# Arduino_Nano_Pinouts.net
KiCad netlist of a schematic drawn in Altium Designer
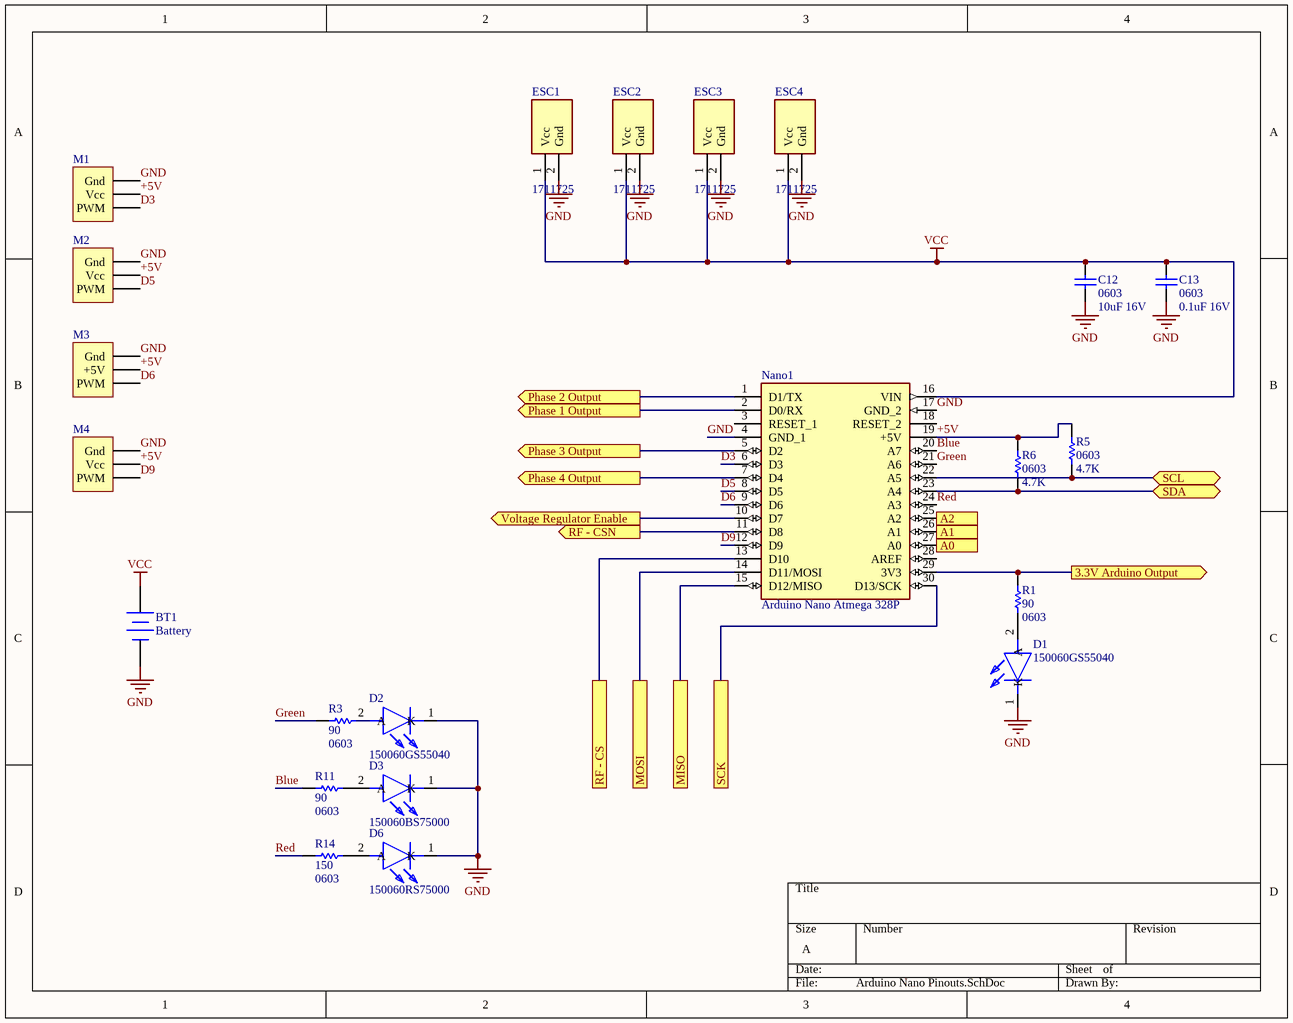
[diagram p0: Arduino Nano Pinouts.SchDoc]

(export (version "E")
  (design (tool "Eeschema 10.0.6"))
  (components
    (comp (ref "BT1")
      (value "Battery")
      (footprint "12AWGBATTCONNECTOR")
      (description "Multicell Battery")
      (fields (field (name "PUBLISHER") "Altium Limited"))
      (libsource (lib "Miscellaneous Devices") (part "Battery"))
    )
    (comp (ref "C12")
      (value "0603")
      (footprint "SMD-0603C")
      (description "Capacitor")
      (fields (field (name "ALTIUM_VALUE") "10uF 16V") (field (name "PUBLISHER") "Altium Limited"))
      (libsource (lib "Miscellaneous Devices") (part "Cap"))
    )
    (comp (ref "C13")
      (value "0603")
      (footprint "SMD-0603C")
      (description "Capacitor")
      (fields (field (name "ALTIUM_VALUE") "0.1uF 16V") (field (name "PUBLISHER") "Altium Limited"))
      (libsource (lib "Miscellaneous Devices") (part "Cap"))
    )
    (comp (ref "D1")
      (value "150060GS55040")
      (footprint "SamacSys:LEDC1608X50N")
      (description "LED")
      (fields
        (field (name "MOUSER PART NUMBER") "710-150060GS55040")
        (field (name "RS PART NUMBER") "1766068P")
      )
      (libsource (lib "*") (part "150060GS55040"))
    )
    (comp (ref "D2")
      (value "150060GS55040")
      (footprint "SamacSys:LEDC1608X50N")
      (description "LED")
      (fields
        (field (name "MOUSER PART NUMBER") "710-150060GS55040")
        (field (name "RS PART NUMBER") "1766068P")
      )
      (libsource (lib "*") (part "150060GS55040"))
    )
    (comp (ref "D3")
      (value "150060BS75000")
      (footprint "SamacSys:LEDC1608X80N")
      (description "LED")
      (fields
        (field (name "MOUSER PART NUMBER") "710-150060BS75000")
        (field (name "RS PART NUMBER") "8154206P")
      )
      (libsource (lib "*") (part "150060BS75000"))
    )
    (comp (ref "D6")
      (value "150060RS75000")
      (footprint "SamacSys:LEDC1608X80N")
      (description "LED")
      (fields
        (field (name "MOUSER PART NUMBER") "710-150060RS75000")
        (field (name "RS PART NUMBER") "8154203P")
      )
      (libsource (lib "*") (part "150060RS75000"))
    )
    (comp (ref "ESC1")
      (value "1711725")
      (footprint "SamacSys:PHEONIX-5.08PITCH-2PIN")
      (description "Integrated Circuit")
      (fields (field (name "MOUSER PART NUMBER") "651-1711725") (field (name "RS PART NUMBER") "1895843"))
      (libsource (lib "*") (part "1711725"))
    )
    (comp (ref "ESC2")
      (value "1711725")
      (footprint "SamacSys:PHEONIX-5.08PITCH-2PIN")
      (description "Integrated Circuit")
      (fields (field (name "MOUSER PART NUMBER") "651-1711725") (field (name "RS PART NUMBER") "1895843"))
      (libsource (lib "*") (part "1711725"))
    )
    (comp (ref "ESC3")
      (value "1711725")
      (footprint "SamacSys:PHEONIX-5.08PITCH-2PIN")
      (description "Integrated Circuit")
      (fields (field (name "MOUSER PART NUMBER") "651-1711725") (field (name "RS PART NUMBER") "1895843"))
      (libsource (lib "*") (part "1711725"))
    )
    (comp (ref "ESC4")
      (value "1711725")
      (footprint "SamacSys:PHEONIX-5.08PITCH-2PIN")
      (description "Integrated Circuit")
      (fields (field (name "MOUSER PART NUMBER") "651-1711725") (field (name "RS PART NUMBER") "1895843"))
      (libsource (lib "*") (part "1711725"))
    )
    (comp (ref "M1")
      (value "~")
      (footprint "*TE_3-644695-3")
      (description "Header, 3-Pin")
      (fields (field (name "PUBLISHER") "Altium Limited"))
      (libsource (lib "Miscellaneous Connectors") (part "Header 3"))
    )
    (comp (ref "M2")
      (value "~")
      (footprint "*TE_3-644695-3")
      (description "Header, 3-Pin")
      (fields (field (name "PUBLISHER") "Altium Limited"))
      (libsource (lib "Miscellaneous Connectors") (part "Header 3"))
    )
    (comp (ref "M3")
      (value "~")
      (footprint "*TE_3-644695-3")
      (description "Header, 3-Pin")
      (fields (field (name "PUBLISHER") "Altium Limited"))
      (libsource (lib "Miscellaneous Connectors") (part "Header 3"))
    )
    (comp (ref "M4")
      (value "~")
      (footprint "*TE_3-644695-3")
      (description "Header, 3-Pin")
      (fields (field (name "PUBLISHER") "Altium Limited"))
      (libsource (lib "Miscellaneous Connectors") (part "Header 3"))
    )
    (comp (ref "Nano1")
      (value "Arduino Nano Atmega 328P")
      (footprint "ARDNanoINV")
      (description "Integrated Circuit")
      (fields
        (field (name "MANUFACTURER_PART_NUMBER") "ARDNanoINV")
        (field (name "MOUSER PART NUMBER") "992-ARD-NANO30")
      )
      (libsource (lib "*") (part "ARDNanoINV"))
    )
    (comp (ref "R1")
      (value "90")
      (footprint "SMD-0603-RES")
      (description "Resistor")
      (fields (field (name "ALTIUM_VALUE") "0603") (field (name "PUBLISHER") "Altium Limited"))
      (libsource (lib "Miscellaneous Devices") (part "Res1"))
    )
    (comp (ref "R3")
      (value "90")
      (footprint "SMD-0603-RES")
      (description "Resistor")
      (fields (field (name "ALTIUM_VALUE") "0603") (field (name "PUBLISHER") "Altium Limited"))
      (libsource (lib "Miscellaneous Devices") (part "Res1"))
    )
    (comp (ref "R5")
      (value "0603")
      (footprint "SMD-0603C")
      (description "Resistor")
      (fields (field (name "ALTIUM_VALUE") "4.7K") (field (name "PUBLISHER") "Altium Limited"))
      (libsource (lib "Miscellaneous Devices") (part "Res1"))
    )
    (comp (ref "R6")
      (value "0603")
      (footprint "SMD-0603-RES")
      (description "Resistor")
      (fields (field (name "ALTIUM_VALUE") "4.7K") (field (name "PUBLISHER") "Altium Limited"))
      (libsource (lib "Miscellaneous Devices") (part "Res1"))
    )
    (comp (ref "R11")
      (value "90")
      (footprint "SMD-0603-RES")
      (description "Resistor")
      (fields (field (name "ALTIUM_VALUE") "0603") (field (name "PUBLISHER") "Altium Limited"))
      (libsource (lib "Miscellaneous Devices") (part "Res1"))
    )
    (comp (ref "R14")
      (value "150")
      (footprint "SMD-0603-RES")
      (description "Resistor")
      (fields (field (name "ALTIUM_VALUE") "0603") (field (name "PUBLISHER") "Altium Limited"))
      (libsource (lib "Miscellaneous Devices") (part "Res1"))
    )
  )
  (nets
    (net (code "1") (name "/+5V") (class "Default")
      (node (ref "M1") (pin "2") (pinfunction "Vcc_2") (pintype "passive"))
      (node (ref "M2") (pin "2") (pinfunction "Vcc_2") (pintype "passive"))
      (node (ref "M3") (pin "2") (pinfunction "Vcc_2") (pintype "passive"))
      (node (ref "M4") (pin "2") (pinfunction "Vcc_2") (pintype "passive"))
      (node (ref "Nano1") (pin "19") (pinfunction "+5V_19") (pintype "power_in"))
      (node (ref "R5") (pin "2") (pinfunction "2_2") (pintype "passive"))
      (node (ref "R6") (pin "2") (pinfunction "2_2") (pintype "passive"))
    )
    (net (code "2") (name "/3.3V Arduino Output") (class "Default")
      (node (ref "Nano1") (pin "29") (pinfunction "3V3_29") (pintype "bidirectional"))
      (node (ref "R1") (pin "1") (pinfunction "1_1") (pintype "passive"))
    )
    (net (code "3") (name "/A0") (class "Default")
      (node (ref "Nano1") (pin "27") (pinfunction "A0_27") (pintype "bidirectional"))
    )
    (net (code "4") (name "/A1") (class "Default")
      (node (ref "Nano1") (pin "26") (pinfunction "A1_26") (pintype "bidirectional"))
    )
    (net (code "5") (name "/A2") (class "Default")
      (node (ref "Nano1") (pin "25") (pinfunction "A2_25") (pintype "bidirectional"))
    )
    (net (code "6") (name "/Blue") (class "Default")
      (node (ref "Nano1") (pin "20") (pinfunction "A7_20") (pintype "bidirectional"))
      (node (ref "R11") (pin "1") (pinfunction "1_1") (pintype "passive"))
    )
    (net (code "7") (name "/D3") (class "Default")
      (node (ref "M1") (pin "1") (pinfunction "PWM_1") (pintype "passive"))
      (node (ref "Nano1") (pin "6") (pinfunction "D3_6") (pintype "bidirectional"))
    )
    (net (code "8") (name "/D5") (class "Default")
      (node (ref "M2") (pin "1") (pinfunction "PWM_1") (pintype "passive"))
      (node (ref "Nano1") (pin "8") (pinfunction "D5_8") (pintype "bidirectional"))
    )
    (net (code "9") (name "/D6") (class "Default")
      (node (ref "M3") (pin "1") (pinfunction "PWM_1") (pintype "passive"))
      (node (ref "Nano1") (pin "9") (pinfunction "D6_9") (pintype "bidirectional"))
    )
    (net (code "10") (name "/D9") (class "Default")
      (node (ref "M4") (pin "1") (pinfunction "PWM_1") (pintype "passive"))
      (node (ref "Nano1") (pin "12") (pinfunction "D9_12") (pintype "bidirectional"))
    )
    (net (code "11") (name "/Green") (class "Default")
      (node (ref "Nano1") (pin "21") (pinfunction "A6_21") (pintype "bidirectional"))
      (node (ref "R3") (pin "1") (pinfunction "1_1") (pintype "passive"))
    )
    (net (code "12") (name "/MISO") (class "Default")
      (node (ref "Nano1") (pin "15") (pinfunction "D12/MISO_15") (pintype "bidirectional"))
    )
    (net (code "13") (name "/MOSI") (class "Default")
      (node (ref "Nano1") (pin "14") (pinfunction "D11/MOSI_14") (pintype "power_in"))
    )
    (net (code "14") (name "/Phase 1 Output") (class "Default")
      (node (ref "Nano1") (pin "2") (pinfunction "D0/RX_2") (pintype "power_in"))
    )
    (net (code "15") (name "/Phase 2 Output") (class "Default")
      (node (ref "Nano1") (pin "1") (pinfunction "D1/TX_1") (pintype "power_in"))
    )
    (net (code "16") (name "/Phase 3 Output") (class "Default")
      (node (ref "Nano1") (pin "5") (pinfunction "D2_5") (pintype "bidirectional"))
    )
    (net (code "17") (name "/Phase 4 Output") (class "Default")
      (node (ref "Nano1") (pin "7") (pinfunction "D4_7") (pintype "bidirectional"))
    )
    (net (code "18") (name "/RF - CS") (class "Default")
      (node (ref "Nano1") (pin "13") (pinfunction "D10_13") (pintype "passive"))
    )
    (net (code "19") (name "/RF - CSN") (class "Default")
      (node (ref "Nano1") (pin "11") (pinfunction "D8_11") (pintype "bidirectional"))
    )
    (net (code "20") (name "/Red") (class "Default")
      (node (ref "Nano1") (pin "24") (pinfunction "A3_24") (pintype "bidirectional"))
      (node (ref "R14") (pin "1") (pinfunction "1_1") (pintype "passive"))
    )
    (net (code "21") (name "/SCK") (class "Default")
      (node (ref "Nano1") (pin "30") (pinfunction "D13/SCK_30") (pintype "bidirectional"))
    )
    (net (code "22") (name "/SCL") (class "Default")
      (node (ref "Nano1") (pin "22") (pinfunction "A5_22") (pintype "bidirectional"))
      (node (ref "R5") (pin "1") (pinfunction "1_1") (pintype "passive"))
    )
    (net (code "23") (name "/SDA") (class "Default")
      (node (ref "Nano1") (pin "23") (pinfunction "A4_23") (pintype "bidirectional"))
      (node (ref "R6") (pin "1") (pinfunction "1_1") (pintype "passive"))
    )
    (net (code "24") (name "/Voltage Regulator Enable") (class "Default")
      (node (ref "Nano1") (pin "10") (pinfunction "D7_10") (pintype "bidirectional"))
    )
    (net (code "25") (name "GND") (class "Default")
      (node (ref "BT1") (pin "2") (pinfunction "-_2") (pintype "passive"))
      (node (ref "C12") (pin "1") (pinfunction "1_1") (pintype "passive"))
      (node (ref "C13") (pin "1") (pinfunction "1_1") (pintype "passive"))
      (node (ref "D1") (pin "1") (pinfunction "K_1") (pintype "passive"))
      (node (ref "D2") (pin "1") (pinfunction "K_1") (pintype "passive"))
      (node (ref "D3") (pin "1") (pinfunction "K_1") (pintype "passive"))
      (node (ref "D6") (pin "1") (pinfunction "K_1") (pintype "passive"))
      (node (ref "ESC1") (pin "2") (pinfunction "Gnd_2") (pintype "passive"))
      (node (ref "ESC2") (pin "2") (pinfunction "Gnd_2") (pintype "passive"))
      (node (ref "ESC3") (pin "2") (pinfunction "Gnd_2") (pintype "passive"))
      (node (ref "ESC4") (pin "2") (pinfunction "Gnd_2") (pintype "passive"))
      (node (ref "M1") (pin "3") (pinfunction "Gnd_3") (pintype "passive"))
      (node (ref "M2") (pin "3") (pinfunction "Gnd_3") (pintype "passive"))
      (node (ref "M3") (pin "3") (pinfunction "Gnd_3") (pintype "passive"))
      (node (ref "M4") (pin "3") (pinfunction "Gnd_3") (pintype "passive"))
      (node (ref "Nano1") (pin "17") (pinfunction "GND_2_17") (pintype "input"))
      (node (ref "Nano1") (pin "4") (pinfunction "GND_1_4") (pintype "power_in"))
    )
    (net (code "26") (name "Net-(D1-A)") (class "Default")
      (node (ref "D1") (pin "2") (pinfunction "A_2") (pintype "passive"))
      (node (ref "R1") (pin "2") (pinfunction "2_2") (pintype "passive"))
    )
    (net (code "27") (name "Net-(D2-A)") (class "Default")
      (node (ref "D2") (pin "2") (pinfunction "A_2") (pintype "passive"))
      (node (ref "R3") (pin "2") (pinfunction "2_2") (pintype "passive"))
    )
    (net (code "28") (name "Net-(D3-A)") (class "Default")
      (node (ref "D3") (pin "2") (pinfunction "A_2") (pintype "passive"))
      (node (ref "R11") (pin "2") (pinfunction "2_2") (pintype "passive"))
    )
    (net (code "29") (name "Net-(D6-A)") (class "Default")
      (node (ref "D6") (pin "2") (pinfunction "A_2") (pintype "passive"))
      (node (ref "R14") (pin "2") (pinfunction "2_2") (pintype "passive"))
    )
    (net (code "30") (name "VCC") (class "Default")
      (node (ref "BT1") (pin "1") (pinfunction "+_1") (pintype "passive"))
      (node (ref "C12") (pin "2") (pinfunction "2_2") (pintype "passive"))
      (node (ref "C13") (pin "2") (pinfunction "2_2") (pintype "passive"))
      (node (ref "ESC1") (pin "1") (pinfunction "Vcc_1") (pintype "passive"))
      (node (ref "ESC2") (pin "1") (pinfunction "Vcc_1") (pintype "passive"))
      (node (ref "ESC3") (pin "1") (pinfunction "Vcc_1") (pintype "passive"))
      (node (ref "ESC4") (pin "1") (pinfunction "Vcc_1") (pintype "passive"))
      (node (ref "Nano1") (pin "16") (pinfunction "VIN_16") (pintype "output"))
    )
    (net (code "31") (name "unconnected-(Nano1-AREF-Pad28)") (class "Default")
      (node (ref "Nano1") (pin "28") (pinfunction "AREF_28") (pintype "bidirectional"))
    )
    (net (code "32") (name "unconnected-(Nano1-RESET_1-Pad3)") (class "Default")
      (node (ref "Nano1") (pin "3") (pinfunction "RESET_1_3") (pintype "passive"))
    )
    (net (code "33") (name "unconnected-(Nano1-RESET_2-Pad18)") (class "Default")
      (node (ref "Nano1") (pin "18") (pinfunction "RESET_2_18") (pintype "passive"))
    )
  )
)
